# pcb_univ_3-_2-7_-_5-0_-x-rev4.net
KiCad netlist of a schematic drawn in EAGLE
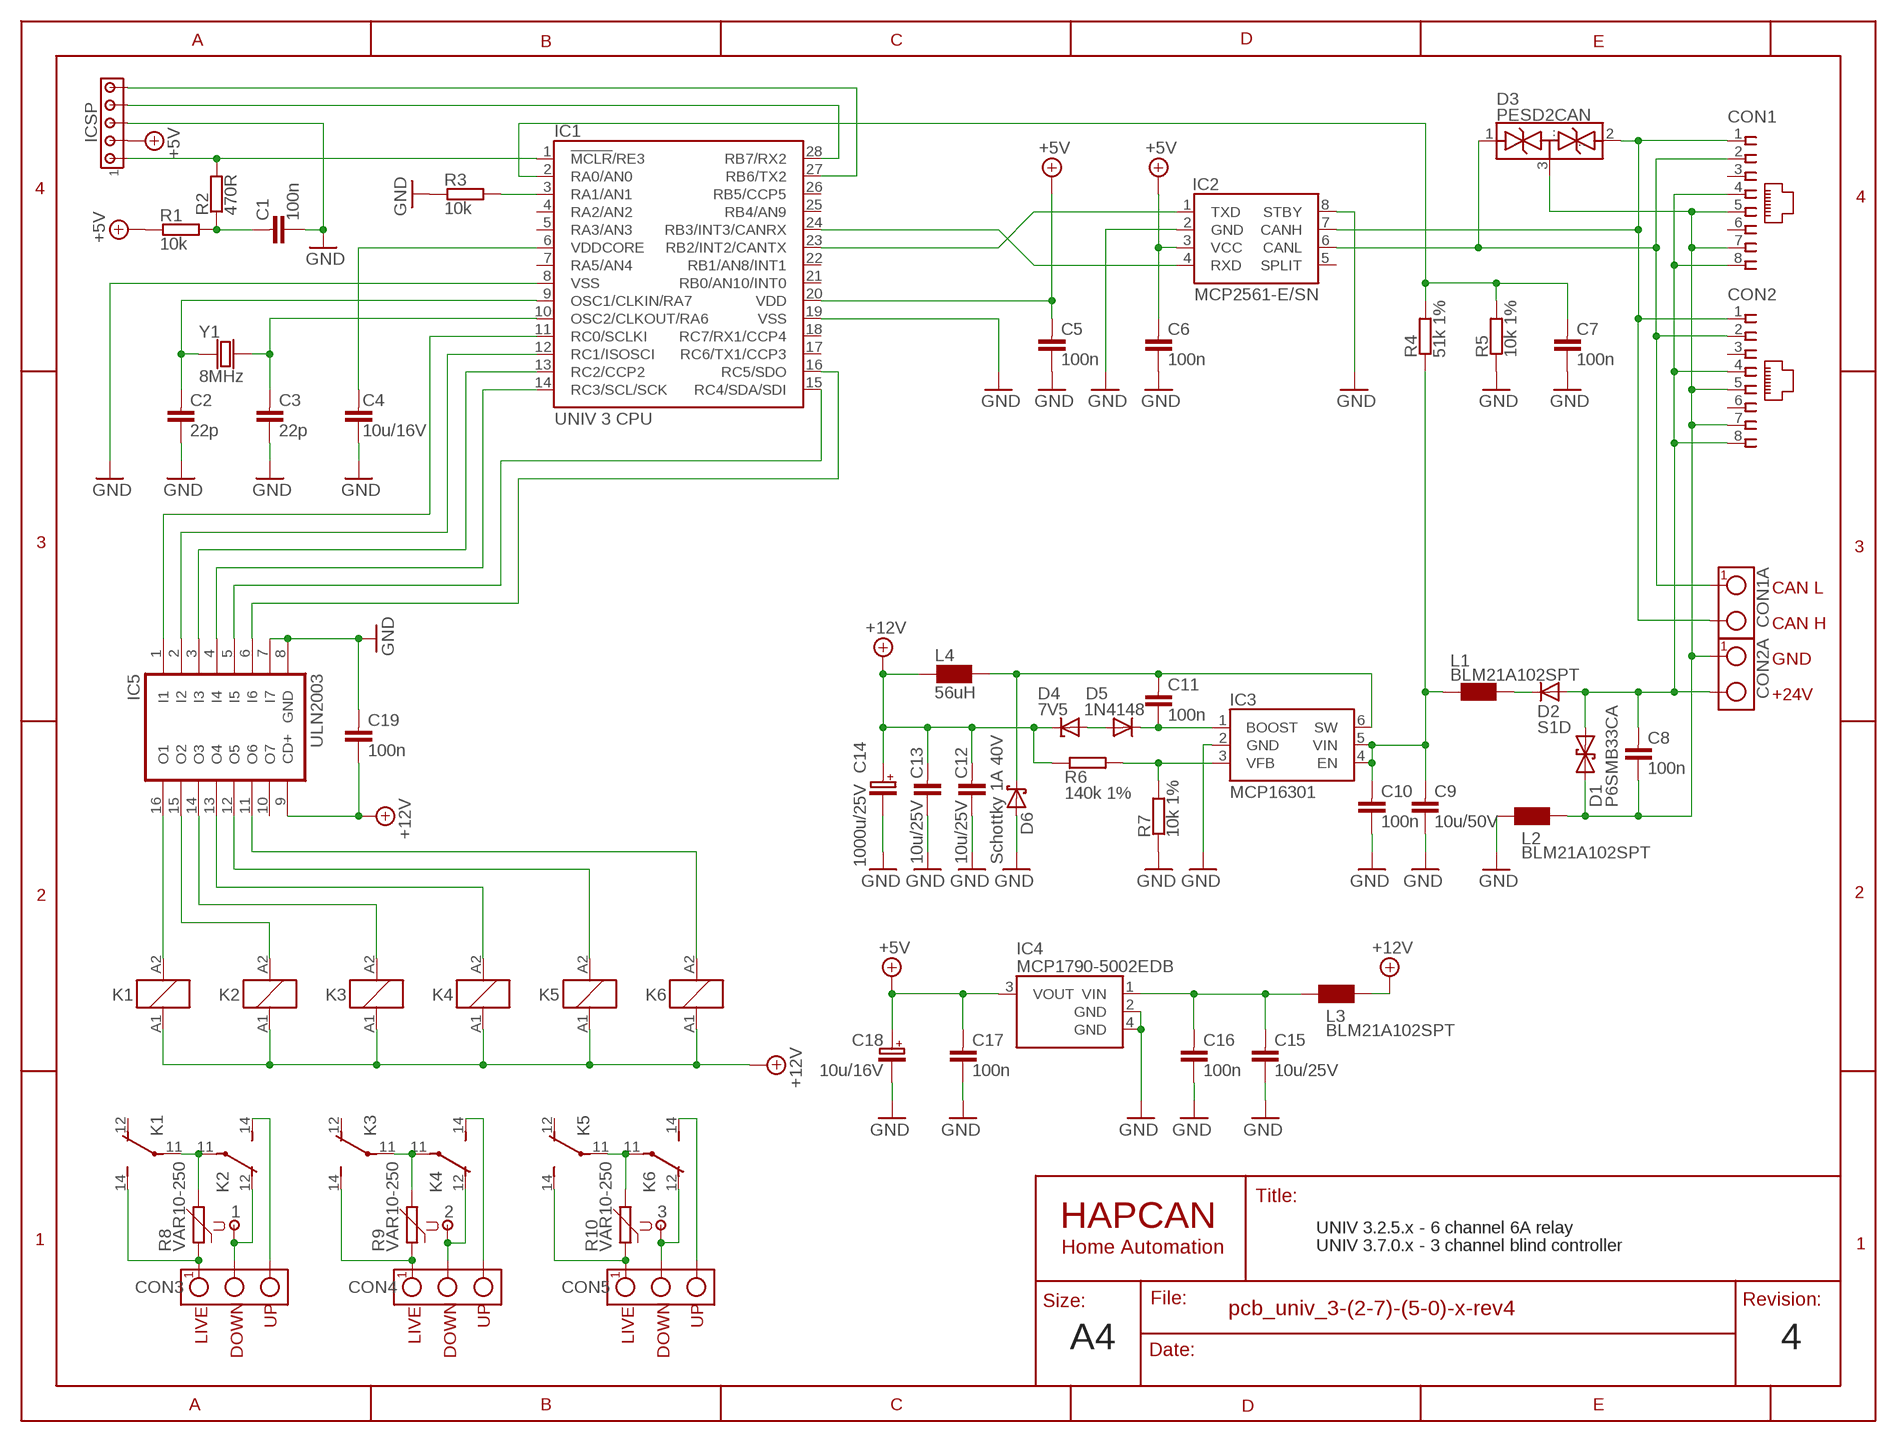
[diagram p0: schematic, sheet 1]

(export (version "E")
  (design (tool "Eeschema 10.0.6"))
  (components
    (comp (ref "1")
      (value "HEADER11X0.9")
      (footprint "eagle-import:SIP-1")
      (libsource (lib "eagle-import") (part "HEADER11X0.9"))
    )
    (comp (ref "2")
      (value "HEADER11X0.9")
      (footprint "eagle-import:SIP-1")
      (libsource (lib "eagle-import") (part "HEADER11X0.9"))
    )
    (comp (ref "3")
      (value "HEADER11X0.9")
      (footprint "eagle-import:SIP-1")
      (libsource (lib "eagle-import") (part "HEADER11X0.9"))
    )
    (comp (ref "C1")
      (value "100n")
      (footprint "eagle-import:0805")
      (libsource (lib "eagle-import") (part "CAPACITOR0805"))
    )
    (comp (ref "C2")
      (value "22p")
      (footprint "eagle-import:0805")
      (libsource (lib "eagle-import") (part "CAPACITOR0805"))
    )
    (comp (ref "C3")
      (value "22p")
      (footprint "eagle-import:0805")
      (libsource (lib "eagle-import") (part "CAPACITOR0805"))
    )
    (comp (ref "C4")
      (value "10u/16V")
      (footprint "eagle-import:0805")
      (libsource (lib "eagle-import") (part "CAPACITOR0805"))
    )
    (comp (ref "C5")
      (value "100n")
      (footprint "eagle-import:0805")
      (libsource (lib "eagle-import") (part "CAPACITOR0805"))
    )
    (comp (ref "C6")
      (value "100n")
      (footprint "eagle-import:0805")
      (libsource (lib "eagle-import") (part "CAPACITOR0805"))
    )
    (comp (ref "C7")
      (value "100n")
      (footprint "eagle-import:0805")
      (libsource (lib "eagle-import") (part "CAPACITOR0805"))
    )
    (comp (ref "C8")
      (value "100n")
      (footprint "eagle-import:0805")
      (libsource (lib "eagle-import") (part "CAPACITOR0805"))
    )
    (comp (ref "C9")
      (value "10u/50V")
      (footprint "eagle-import:1210")
      (libsource (lib "eagle-import") (part "CAPACITOR1210"))
    )
    (comp (ref "C10")
      (value "100n")
      (footprint "eagle-import:0805")
      (libsource (lib "eagle-import") (part "CAPACITOR0805"))
    )
    (comp (ref "C11")
      (value "100n")
      (footprint "eagle-import:0805")
      (libsource (lib "eagle-import") (part "CAPACITOR0805"))
    )
    (comp (ref "C12")
      (value "10u/25V")
      (footprint "eagle-import:1206")
      (libsource (lib "eagle-import") (part "CAPACITOR1206"))
    )
    (comp (ref "C13")
      (value "10u/25V")
      (footprint "eagle-import:1206")
      (libsource (lib "eagle-import") (part "CAPACITOR1206"))
    )
    (comp (ref "C14")
      (value "1000u/25V")
      (footprint "eagle-import:CAP-5X10.5")
      (libsource (lib "eagle-import") (part "CAPACITOR-POLARIZED-5X10.5"))
    )
    (comp (ref "C15")
      (value "10u/25V")
      (footprint "eagle-import:1206")
      (libsource (lib "eagle-import") (part "CAPACITOR1206"))
    )
    (comp (ref "C16")
      (value "100n")
      (footprint "eagle-import:0805")
      (libsource (lib "eagle-import") (part "CAPACITOR0805"))
    )
    (comp (ref "C17")
      (value "100n")
      (footprint "eagle-import:0805")
      (libsource (lib "eagle-import") (part "CAPACITOR0805"))
    )
    (comp (ref "C18")
      (value "10u/16V")
      (footprint "eagle-import:SMC_B")
      (libsource (lib "eagle-import") (part "CAPACITOR-POLARIZED-SMC_B"))
    )
    (comp (ref "C19")
      (value "100n")
      (footprint "eagle-import:0805")
      (libsource (lib "eagle-import") (part "CAPACITOR0805"))
    )
    (comp (ref "CON1")
      (value "RJ45-SOCKET")
      (footprint "eagle-import:RJ45-PCB-SOCKET")
      (libsource (lib "eagle-import") (part "RJ45-SOCKET"))
    )
    (comp (ref "CON1A")
      (value "TERMINAL-2")
      (footprint "eagle-import:ARK2-5X10,5MM")
      (libsource (lib "eagle-import") (part "TERMINAL-2-5X10,5MM"))
    )
    (comp (ref "CON2")
      (value "RJ45-SOCKET")
      (footprint "eagle-import:RJ45-PCB-SOCKET")
      (libsource (lib "eagle-import") (part "RJ45-SOCKET"))
    )
    (comp (ref "CON2A")
      (value "TERMINAL-2")
      (footprint "eagle-import:ARK2-5X10,5MM")
      (libsource (lib "eagle-import") (part "TERMINAL-2-5X10,5MM"))
    )
    (comp (ref "CON3")
      (value "TERMINAL-3-5X10.5MM")
      (footprint "eagle-import:ARK3-5X10.5MM")
      (libsource (lib "eagle-import") (part "TERMINAL-3-5X10.5MM"))
    )
    (comp (ref "CON4")
      (value "TERMINAL-3-5X10.5MM")
      (footprint "eagle-import:ARK3-5X10.5MM")
      (libsource (lib "eagle-import") (part "TERMINAL-3-5X10.5MM"))
    )
    (comp (ref "CON5")
      (value "TERMINAL-3-5X10.5MM")
      (footprint "eagle-import:ARK3-5X10.5MM")
      (libsource (lib "eagle-import") (part "TERMINAL-3-5X10.5MM"))
    )
    (comp (ref "D1")
      (value "P6SMB33CA")
      (footprint "eagle-import:DO-214_TRANSIL2")
      (libsource (lib "eagle-import") (part "DIODE_TRANSIL2"))
    )
    (comp (ref "D2")
      (value "S1D")
      (footprint "eagle-import:DO-214")
      (libsource (lib "eagle-import") (part "DIODE_DO-214"))
    )
    (comp (ref "D3")
      (value "PESD2CAN")
      (footprint "eagle-import:SOT-23")
      (libsource (lib "eagle-import") (part "PESD2CANSOT-23"))
    )
    (comp (ref "D4")
      (value "7V5")
      (footprint "eagle-import:SOD-80")
      (libsource (lib "eagle-import") (part "DIODE_ZENER_SOD-80"))
    )
    (comp (ref "D5")
      (value "1N4148")
      (footprint "eagle-import:0805")
      (libsource (lib "eagle-import") (part "DIODE_0805"))
    )
    (comp (ref "D6")
      (value "Schottky 1A 40V")
      (footprint "eagle-import:DO-214")
      (libsource (lib "eagle-import") (part "DIODE_TRANSIL1_DO214"))
    )
    (comp (ref "IC1")
      (value "UNIV 3 CPU")
      (footprint "eagle-import:UNIV3CPU")
      (libsource (lib "eagle-import") (part "UNIV3CPU-I/SO"))
    )
    (comp (ref "IC2")
      (value "MCP2561-E/SN")
      (footprint "eagle-import:SO-08")
      (libsource (lib "eagle-import") (part "MCP2561-E/SN"))
    )
    (comp (ref "IC3")
      (value "MCP16301")
      (footprint "eagle-import:SOT-23-6")
      (libsource (lib "eagle-import") (part "MCP16301SOT23-6"))
    )
    (comp (ref "IC4")
      (value "MCP1790-5002EDB")
      (footprint "eagle-import:SOT-223")
      (libsource (lib "eagle-import") (part "MCP1826SOT223-3"))
    )
    (comp (ref "IC5")
      (value "ULN2003")
      (footprint "eagle-import:SO-16")
      (libsource (lib "eagle-import") (part "ULN2003"))
    )
    (comp (ref "ICSP")
      (value "HEADER5")
      (footprint "eagle-import:SIP-5")
      (libsource (lib "eagle-import") (part "HEADER5"))
    )
    (comp (ref "K1")
      (value "RELAY_SNR_SPDTV")
      (footprint "eagle-import:RELAY_SNR_SPDT_V")
      (libsource (lib "eagle-import") (part "RELAY_SNR_SPDTV"))
    )
    (comp (ref "K2")
      (value "RELAY_SNR_SPDTV")
      (footprint "eagle-import:RELAY_SNR_SPDT_V")
      (libsource (lib "eagle-import") (part "RELAY_SNR_SPDTV"))
    )
    (comp (ref "K3")
      (value "RELAY_SNR_SPDTV")
      (footprint "eagle-import:RELAY_SNR_SPDT_V")
      (libsource (lib "eagle-import") (part "RELAY_SNR_SPDTV"))
    )
    (comp (ref "K4")
      (value "RELAY_SNR_SPDTV")
      (footprint "eagle-import:RELAY_SNR_SPDT_V")
      (libsource (lib "eagle-import") (part "RELAY_SNR_SPDTV"))
    )
    (comp (ref "K5")
      (value "RELAY_SNR_SPDTV")
      (footprint "eagle-import:RELAY_SNR_SPDT_V")
      (libsource (lib "eagle-import") (part "RELAY_SNR_SPDTV"))
    )
    (comp (ref "K6")
      (value "RELAY_SNR_SPDTV")
      (footprint "eagle-import:RELAY_SNR_SPDT_V")
      (libsource (lib "eagle-import") (part "RELAY_SNR_SPDTV"))
    )
    (comp (ref "L1")
      (value "BLM21A102SPT")
      (footprint "eagle-import:0805")
      (libsource (lib "eagle-import") (part "CHOKE0805"))
    )
    (comp (ref "L2")
      (value "BLM21A102SPT")
      (footprint "eagle-import:0805")
      (libsource (lib "eagle-import") (part "CHOKE0805"))
    )
    (comp (ref "L3")
      (value "BLM21A102SPT")
      (footprint "eagle-import:0805")
      (libsource (lib "eagle-import") (part "CHOKE0805"))
    )
    (comp (ref "L4")
      (value "56uH")
      (footprint "eagle-import:CHOKE-DER0705")
      (libsource (lib "eagle-import") (part "CHOKEDER0705"))
    )
    (comp (ref "R1")
      (value "10k")
      (footprint "eagle-import:0805")
      (libsource (lib "eagle-import") (part "RESISTOR0805"))
    )
    (comp (ref "R2")
      (value "470R")
      (footprint "eagle-import:0805")
      (libsource (lib "eagle-import") (part "RESISTOR0805"))
    )
    (comp (ref "R3")
      (value "10k")
      (footprint "eagle-import:0805")
      (libsource (lib "eagle-import") (part "RESISTOR0805"))
    )
    (comp (ref "R4")
      (value "51k 1%")
      (footprint "eagle-import:0805")
      (libsource (lib "eagle-import") (part "RESISTOR0805"))
    )
    (comp (ref "R5")
      (value "10k 1%")
      (footprint "eagle-import:0805")
      (libsource (lib "eagle-import") (part "RESISTOR0805"))
    )
    (comp (ref "R6")
      (value "140k 1%")
      (footprint "eagle-import:0805")
      (libsource (lib "eagle-import") (part "RESISTOR0805"))
    )
    (comp (ref "R7")
      (value "10k 1%")
      (footprint "eagle-import:0805")
      (libsource (lib "eagle-import") (part "RESISTOR0805"))
    )
    (comp (ref "R8")
      (value "VAR10-250")
      (footprint "eagle-import:VARISTOR1")
      (libsource (lib "eagle-import") (part "VARISTOR7.5MM-1"))
    )
    (comp (ref "R9")
      (value "VAR10-250")
      (footprint "eagle-import:VARISTOR1")
      (libsource (lib "eagle-import") (part "VARISTOR7.5MM-1"))
    )
    (comp (ref "R10")
      (value "VAR10-250")
      (footprint "eagle-import:VARISTOR1")
      (libsource (lib "eagle-import") (part "VARISTOR7.5MM-1"))
    )
    (comp (ref "Y1")
      (value "8MHz")
      (footprint "eagle-import:CRYSTAL-HC49V")
      (libsource (lib "eagle-import") (part "CRYSTAL-HC49V"))
    )
  )
  (nets
    (net (code "1") (name "+5V") (class "Default")
      (node (ref "C17") (pin "1") (pinfunction "1_1") (pintype "passive"))
      (node (ref "C18") (pin "+") (pinfunction "1_+") (pintype "passive"))
      (node (ref "C5") (pin "1") (pinfunction "1_1") (pintype "passive"))
      (node (ref "C6") (pin "1") (pinfunction "1_1") (pintype "passive"))
      (node (ref "IC1") (pin "20") (pinfunction "VDD_20") (pintype "bidirectional"))
      (node (ref "IC2") (pin "3") (pinfunction "VCC_3") (pintype "bidirectional"))
      (node (ref "IC4") (pin "3") (pinfunction "VOUT_3") (pintype "bidirectional"))
      (node (ref "ICSP") (pin "2") (pinfunction "2_2") (pintype "passive"))
      (node (ref "R1") (pin "1") (pinfunction "1_1") (pintype "passive"))
    )
    (net (code "2") (name "+12V") (class "Default")
      (node (ref "C12") (pin "1") (pinfunction "1_1") (pintype "passive"))
      (node (ref "C13") (pin "1") (pinfunction "1_1") (pintype "passive"))
      (node (ref "C14") (pin "+") (pinfunction "1_+") (pintype "passive"))
      (node (ref "C19") (pin "2") (pinfunction "2_2") (pintype "passive"))
      (node (ref "D4") (pin "C") (pinfunction "C_C") (pintype "passive"))
      (node (ref "IC5") (pin "9") (pinfunction "CD+_9") (pintype "passive"))
      (node (ref "K1") (pin "A1") (pinfunction "1_A1") (pintype "passive"))
      (node (ref "K2") (pin "A1") (pinfunction "1_A1") (pintype "passive"))
      (node (ref "K3") (pin "A1") (pinfunction "1_A1") (pintype "passive"))
      (node (ref "K4") (pin "A1") (pinfunction "1_A1") (pintype "passive"))
      (node (ref "K5") (pin "A1") (pinfunction "1_A1") (pintype "passive"))
      (node (ref "K6") (pin "A1") (pinfunction "1_A1") (pintype "passive"))
      (node (ref "L3") (pin "2") (pinfunction "2_2") (pintype "passive"))
      (node (ref "L4") (pin "1") (pinfunction "1_1") (pintype "passive"))
      (node (ref "R6") (pin "1") (pinfunction "1_1") (pintype "passive"))
    )
    (net (code "3") (name "GND") (class "Default")
      (node (ref "C1") (pin "2") (pinfunction "2_2") (pintype "passive"))
      (node (ref "C10") (pin "2") (pinfunction "2_2") (pintype "passive"))
      (node (ref "C12") (pin "2") (pinfunction "2_2") (pintype "passive"))
      (node (ref "C13") (pin "2") (pinfunction "2_2") (pintype "passive"))
      (node (ref "C14") (pin "-") (pinfunction "2_-") (pintype "passive"))
      (node (ref "C15") (pin "2") (pinfunction "2_2") (pintype "passive"))
      (node (ref "C16") (pin "2") (pinfunction "2_2") (pintype "passive"))
      (node (ref "C17") (pin "2") (pinfunction "2_2") (pintype "passive"))
      (node (ref "C18") (pin "-") (pinfunction "2_-") (pintype "passive"))
      (node (ref "C19") (pin "1") (pinfunction "1_1") (pintype "passive"))
      (node (ref "C2") (pin "2") (pinfunction "2_2") (pintype "passive"))
      (node (ref "C3") (pin "2") (pinfunction "2_2") (pintype "passive"))
      (node (ref "C4") (pin "2") (pinfunction "2_2") (pintype "passive"))
      (node (ref "C5") (pin "2") (pinfunction "2_2") (pintype "passive"))
      (node (ref "C6") (pin "2") (pinfunction "2_2") (pintype "passive"))
      (node (ref "C7") (pin "2") (pinfunction "2_2") (pintype "passive"))
      (node (ref "C9") (pin "2") (pinfunction "2_2") (pintype "passive"))
      (node (ref "D6") (pin "A") (pinfunction "A_A") (pintype "passive"))
      (node (ref "IC1") (pin "19") (pinfunction "VSS_19") (pintype "bidirectional"))
      (node (ref "IC1") (pin "8") (pinfunction "VSS_8") (pintype "bidirectional"))
      (node (ref "IC2") (pin "2") (pinfunction "GND_2") (pintype "bidirectional"))
      (node (ref "IC2") (pin "8") (pinfunction "STBY_8") (pintype "bidirectional"))
      (node (ref "IC3") (pin "2") (pinfunction "GND_2") (pintype "bidirectional"))
      (node (ref "IC4") (pin "2") (pinfunction "GND_2") (pintype "bidirectional"))
      (node (ref "IC4") (pin "4") (pinfunction "GND_4") (pintype "bidirectional"))
      (node (ref "IC5") (pin "7") (pinfunction "I7_7") (pintype "input"))
      (node (ref "IC5") (pin "8") (pinfunction "GND_8") (pintype "power_in"))
      (node (ref "ICSP") (pin "3") (pinfunction "3_3") (pintype "passive"))
      (node (ref "L2") (pin "1") (pinfunction "1_1") (pintype "passive"))
      (node (ref "R3") (pin "1") (pinfunction "1_1") (pintype "passive"))
      (node (ref "R5") (pin "1") (pinfunction "1_1") (pintype "passive"))
      (node (ref "R7") (pin "1") (pinfunction "1_1") (pintype "passive"))
    )
    (net (code "4") (name "Net-(C1-Pad1)") (class "Default")
      (node (ref "C1") (pin "1") (pinfunction "1_1") (pintype "passive"))
      (node (ref "R1") (pin "2") (pinfunction "2_2") (pintype "passive"))
      (node (ref "R2") (pin "1") (pinfunction "1_1") (pintype "passive"))
    )
    (net (code "5") (name "Net-(D1-1)") (class "Default")
      (node (ref "C8") (pin "2") (pinfunction "2_2") (pintype "passive"))
      (node (ref "CON1") (pin "5") (pinfunction "5_5") (pintype "passive"))
      (node (ref "CON1") (pin "7") (pinfunction "7_7") (pintype "passive"))
      (node (ref "CON2") (pin "5") (pinfunction "5_5") (pintype "passive"))
      (node (ref "CON2") (pin "7") (pinfunction "7_7") (pintype "passive"))
      (node (ref "CON2A") (pin "1") (pinfunction "1_1") (pintype "passive"))
      (node (ref "D1") (pin "A") (pinfunction "1_A") (pintype "passive"))
      (node (ref "D3") (pin "3") (pinfunction "..._3") (pintype "bidirectional"))
      (node (ref "L2") (pin "2") (pinfunction "2_2") (pintype "passive"))
    )
    (net (code "6") (name "Net-(D1-2)") (class "Default")
      (node (ref "C8") (pin "1") (pinfunction "1_1") (pintype "passive"))
      (node (ref "CON1") (pin "4") (pinfunction "4_4") (pintype "passive"))
      (node (ref "CON1") (pin "8") (pinfunction "8_8") (pintype "passive"))
      (node (ref "CON2") (pin "4") (pinfunction "4_4") (pintype "passive"))
      (node (ref "CON2") (pin "8") (pinfunction "8_8") (pintype "passive"))
      (node (ref "CON2A") (pin "2") (pinfunction "2_2") (pintype "passive"))
      (node (ref "D1") (pin "C") (pinfunction "2_C") (pintype "passive"))
      (node (ref "D2") (pin "A") (pinfunction "A_A") (pintype "passive"))
    )
    (net (code "7") (name "Net-(D2-PadC)") (class "Default")
      (node (ref "D2") (pin "C") (pinfunction "C_C") (pintype "passive"))
      (node (ref "L1") (pin "2") (pinfunction "2_2") (pintype "passive"))
    )
    (net (code "8") (name "Net-(D3-.)") (class "Default")
      (node (ref "CON1") (pin "2") (pinfunction "2_2") (pintype "passive"))
      (node (ref "CON1A") (pin "1") (pinfunction "1_1") (pintype "passive"))
      (node (ref "CON2") (pin "2") (pinfunction "2_2") (pintype "passive"))
      (node (ref "D3") (pin "1") (pinfunction "._1") (pintype "bidirectional"))
      (node (ref "IC2") (pin "6") (pinfunction "CANL_6") (pintype "bidirectional"))
    )
    (net (code "9") (name "Net-(D3-..)") (class "Default")
      (node (ref "CON1") (pin "1") (pinfunction "1_1") (pintype "passive"))
      (node (ref "CON1A") (pin "2") (pinfunction "2_2") (pintype "passive"))
      (node (ref "CON2") (pin "1") (pinfunction "1_1") (pintype "passive"))
      (node (ref "D3") (pin "2") (pinfunction ".._2") (pintype "bidirectional"))
      (node (ref "IC2") (pin "7") (pinfunction "CANH_7") (pintype "bidirectional"))
    )
    (net (code "10") (name "Net-(D5-A)") (class "Default")
      (node (ref "D4") (pin "A") (pinfunction "A_A") (pintype "passive"))
      (node (ref "D5") (pin "2") (pinfunction "A_2") (pintype "passive"))
    )
    (net (code "11") (name "Net-(D5-C)") (class "Default")
      (node (ref "C11") (pin "2") (pinfunction "2_2") (pintype "passive"))
      (node (ref "D5") (pin "1") (pinfunction "C_1") (pintype "passive"))
      (node (ref "IC3") (pin "1") (pinfunction "BOOST_1") (pintype "bidirectional"))
    )
    (net (code "12") (name "Net-(IC1-OSC1{slash}CLKIN{slash}RA7)") (class "Default")
      (node (ref "C2") (pin "1") (pinfunction "1_1") (pintype "passive"))
      (node (ref "IC1") (pin "9") (pinfunction "OSC1/CLKIN/RA7_9") (pintype "bidirectional"))
      (node (ref "Y1") (pin "1") (pinfunction "1_1") (pintype "passive"))
    )
    (net (code "13") (name "Net-(IC1-OSC2{slash}CLKOUT{slash}RA6)") (class "Default")
      (node (ref "C3") (pin "1") (pinfunction "1_1") (pintype "passive"))
      (node (ref "IC1") (pin "10") (pinfunction "OSC2/CLKOUT/RA6_10") (pintype "bidirectional"))
      (node (ref "Y1") (pin "2") (pinfunction "2_2") (pintype "passive"))
    )
    (net (code "14") (name "Net-(IC1-RA0{slash}AN0)") (class "Default")
      (node (ref "C7") (pin "1") (pinfunction "1_1") (pintype "passive"))
      (node (ref "IC1") (pin "2") (pinfunction "RA0/AN0_2") (pintype "bidirectional"))
      (node (ref "R4") (pin "2") (pinfunction "2_2") (pintype "passive"))
      (node (ref "R5") (pin "2") (pinfunction "2_2") (pintype "passive"))
    )
    (net (code "15") (name "Net-(IC1-RA1{slash}AN1)") (class "Default")
      (node (ref "IC1") (pin "3") (pinfunction "RA1/AN1_3") (pintype "bidirectional"))
      (node (ref "R3") (pin "2") (pinfunction "2_2") (pintype "passive"))
    )
    (net (code "16") (name "Net-(IC1-RB2{slash}INT2{slash}CANTX)") (class "Default")
      (node (ref "IC1") (pin "23") (pinfunction "RB2/INT2/CANTX_23") (pintype "bidirectional"))
      (node (ref "IC2") (pin "1") (pinfunction "TXD_1") (pintype "bidirectional"))
    )
    (net (code "17") (name "Net-(IC1-RB3{slash}INT3{slash}CANRX)") (class "Default")
      (node (ref "IC1") (pin "24") (pinfunction "RB3/INT3/CANRX_24") (pintype "bidirectional"))
      (node (ref "IC2") (pin "4") (pinfunction "RXD_4") (pintype "bidirectional"))
    )
    (net (code "18") (name "Net-(IC1-RB6{slash}TX2)") (class "Default")
      (node (ref "IC1") (pin "27") (pinfunction "RB6/TX2_27") (pintype "bidirectional"))
      (node (ref "ICSP") (pin "5") (pinfunction "5_5") (pintype "passive"))
    )
    (net (code "19") (name "Net-(IC1-RB7{slash}RX2)") (class "Default")
      (node (ref "IC1") (pin "28") (pinfunction "RB7/RX2_28") (pintype "bidirectional"))
      (node (ref "ICSP") (pin "4") (pinfunction "4_4") (pintype "passive"))
    )
    (net (code "20") (name "Net-(IC1-RC0{slash}SCLKI)") (class "Default")
      (node (ref "IC1") (pin "11") (pinfunction "RC0/SCLKI_11") (pintype "bidirectional"))
      (node (ref "IC5") (pin "1") (pinfunction "I1_1") (pintype "input"))
    )
    (net (code "21") (name "Net-(IC1-RC1{slash}ISOSCI)") (class "Default")
      (node (ref "IC1") (pin "12") (pinfunction "RC1/ISOSCI_12") (pintype "bidirectional"))
      (node (ref "IC5") (pin "2") (pinfunction "I2_2") (pintype "input"))
    )
    (net (code "22") (name "Net-(IC1-RC2{slash}CCP2)") (class "Default")
      (node (ref "IC1") (pin "13") (pinfunction "RC2/CCP2_13") (pintype "bidirectional"))
      (node (ref "IC5") (pin "3") (pinfunction "I3_3") (pintype "input"))
    )
    (net (code "23") (name "Net-(IC1-RC3{slash}SCL{slash}SCK)") (class "Default")
      (node (ref "IC1") (pin "14") (pinfunction "RC3/SCL/SCK_14") (pintype "bidirectional"))
      (node (ref "IC5") (pin "4") (pinfunction "I4_4") (pintype "input"))
    )
    (net (code "24") (name "Net-(IC1-RC4{slash}SDA{slash}SDI)") (class "Default")
      (node (ref "IC1") (pin "15") (pinfunction "RC4/SDA/SDI_15") (pintype "bidirectional"))
      (node (ref "IC5") (pin "5") (pinfunction "I5_5") (pintype "input"))
    )
    (net (code "25") (name "Net-(IC1-RC5{slash}SDO)") (class "Default")
      (node (ref "IC1") (pin "16") (pinfunction "RC5/SDO_16") (pintype "bidirectional"))
      (node (ref "IC5") (pin "6") (pinfunction "I6_6") (pintype "input"))
    )
    (net (code "26") (name "Net-(IC1-VDDCORE)") (class "Default")
      (node (ref "C4") (pin "1") (pinfunction "1_1") (pintype "passive"))
      (node (ref "IC1") (pin "6") (pinfunction "VDDCORE_6") (pintype "bidirectional"))
    )
    (net (code "27") (name "Net-(IC1-~{MCLR}{slash}RE3)") (class "Default")
      (node (ref "IC1") (pin "1") (pinfunction "~{MCLR}/RE3_1") (pintype "bidirectional"))
      (node (ref "ICSP") (pin "1") (pinfunction "1_1") (pintype "passive"))
      (node (ref "R2") (pin "2") (pinfunction "2_2") (pintype "passive"))
    )
    (net (code "28") (name "Net-(IC3-EN)") (class "Default")
      (node (ref "C10") (pin "1") (pinfunction "1_1") (pintype "passive"))
      (node (ref "C9") (pin "1") (pinfunction "1_1") (pintype "passive"))
      (node (ref "IC3") (pin "4") (pinfunction "EN_4") (pintype "bidirectional"))
      (node (ref "IC3") (pin "5") (pinfunction "VIN_5") (pintype "bidirectional"))
      (node (ref "L1") (pin "1") (pinfunction "1_1") (pintype "passive"))
      (node (ref "R4") (pin "1") (pinfunction "1_1") (pintype "passive"))
    )
    (net (code "29") (name "Net-(IC3-SW)") (class "Default")
      (node (ref "C11") (pin "1") (pinfunction "1_1") (pintype "passive"))
      (node (ref "D6") (pin "C") (pinfunction "C_C") (pintype "passive"))
      (node (ref "IC3") (pin "6") (pinfunction "SW_6") (pintype "bidirectional"))
      (node (ref "L4") (pin "2") (pinfunction "2_2") (pintype "passive"))
    )
    (net (code "30") (name "Net-(IC3-VFB)") (class "Default")
      (node (ref "IC3") (pin "3") (pinfunction "VFB_3") (pintype "bidirectional"))
      (node (ref "R6") (pin "2") (pinfunction "2_2") (pintype "passive"))
      (node (ref "R7") (pin "2") (pinfunction "2_2") (pintype "passive"))
    )
    (net (code "31") (name "Net-(IC4-VIN)") (class "Default")
      (node (ref "C15") (pin "1") (pinfunction "1_1") (pintype "passive"))
      (node (ref "C16") (pin "1") (pinfunction "1_1") (pintype "passive"))
      (node (ref "IC4") (pin "1") (pinfunction "VIN_1") (pintype "bidirectional"))
      (node (ref "L3") (pin "1") (pinfunction "1_1") (pintype "passive"))
    )
    (net (code "32") (name "Net-(IC5-O1)") (class "Default")
      (node (ref "IC5") (pin "16") (pinfunction "O1_16") (pintype "open_collector"))
      (node (ref "K1") (pin "A2") (pinfunction "2_A2") (pintype "passive"))
    )
    (net (code "33") (name "Net-(IC5-O2)") (class "Default")
      (node (ref "IC5") (pin "15") (pinfunction "O2_15") (pintype "open_collector"))
      (node (ref "K2") (pin "A2") (pinfunction "2_A2") (pintype "passive"))
    )
    (net (code "34") (name "Net-(IC5-O3)") (class "Default")
      (node (ref "IC5") (pin "14") (pinfunction "O3_14") (pintype "open_collector"))
      (node (ref "K3") (pin "A2") (pinfunction "2_A2") (pintype "passive"))
    )
    (net (code "35") (name "Net-(IC5-O4)") (class "Default")
      (node (ref "IC5") (pin "13") (pinfunction "O4_13") (pintype "open_collector"))
      (node (ref "K4") (pin "A2") (pinfunction "2_A2") (pintype "passive"))
    )
    (net (code "36") (name "Net-(IC5-O5)") (class "Default")
      (node (ref "IC5") (pin "12") (pinfunction "O5_12") (pintype "open_collector"))
      (node (ref "K5") (pin "A2") (pinfunction "2_A2") (pintype "passive"))
    )
    (net (code "37") (name "Net-(IC5-O6)") (class "Default")
      (node (ref "IC5") (pin "11") (pinfunction "O6_11") (pintype "open_collector"))
      (node (ref "K6") (pin "A2") (pinfunction "2_A2") (pintype "passive"))
    )
    (net (code "38") (name "Net-(K1B-COM)") (class "Default")
      (node (ref "K1") (pin "11") (pinfunction "COM_11") (pintype "passive"))
      (node (ref "K2") (pin "11") (pinfunction "COM_11") (pintype "passive"))
      (node (ref "R8") (pin "2") (pinfunction "2_2") (pintype "passive"))
    )
    (net (code "39") (name "Net-(K1B-NO)") (class "Default")
      (node (ref "CON3") (pin "1") (pinfunction "1_1") (pintype "passive"))
      (node (ref "K1") (pin "14") (pinfunction "NO_14") (pintype "passive"))
      (node (ref "R8") (pin "1") (pinfunction "1_1") (pintype "passive"))
    )
    (net (code "40") (name "Net-(K2B-NC)") (class "Default")
      (node (ref "1") (pin "1") (pinfunction "1_1") (pintype "passive"))
      (node (ref "CON3") (pin "2") (pinfunction "2_2") (pintype "passive"))
      (node (ref "K2") (pin "12") (pinfunction "NC_12") (pintype "passive"))
    )
    (net (code "41") (name "Net-(K2B-NO)") (class "Default")
      (node (ref "CON3") (pin "3") (pinfunction "3_3") (pintype "passive"))
      (node (ref "K2") (pin "14") (pinfunction "NO_14") (pintype "passive"))
    )
    (net (code "42") (name "Net-(K3B-COM)") (class "Default")
      (node (ref "K3") (pin "11") (pinfunction "COM_11") (pintype "passive"))
      (node (ref "K4") (pin "11") (pinfunction "COM_11") (pintype "passive"))
      (node (ref "R9") (pin "2") (pinfunction "2_2") (pintype "passive"))
    )
    (net (code "43") (name "Net-(K3B-NO)") (class "Default")
      (node (ref "CON4") (pin "1") (pinfunction "1_1") (pintype "passive"))
      (node (ref "K3") (pin "14") (pinfunction "NO_14") (pintype "passive"))
      (node (ref "R9") (pin "1") (pinfunction "1_1") (pintype "passive"))
    )
    (net (code "44") (name "Net-(K4B-NC)") (class "Default")
      (node (ref "2") (pin "1") (pinfunction "1_1") (pintype "passive"))
      (node (ref "CON4") (pin "2") (pinfunction "2_2") (pintype "passive"))
      (node (ref "K4") (pin "12") (pinfunction "NC_12") (pintype "passive"))
    )
    (net (code "45") (name "Net-(K4B-NO)") (class "Default")
      (node (ref "CON4") (pin "3") (pinfunction "3_3") (pintype "passive"))
      (node (ref "K4") (pin "14") (pinfunction "NO_14") (pintype "passive"))
    )
    (net (code "46") (name "Net-(K5B-COM)") (class "Default")
      (node (ref "K5") (pin "11") (pinfunction "COM_11") (pintype "passive"))
      (node (ref "K6") (pin "11") (pinfunction "COM_11") (pintype "passive"))
      (node (ref "R10") (pin "2") (pinfunction "2_2") (pintype "passive"))
    )
    (net (code "47") (name "Net-(K5B-NO)") (class "Default")
      (node (ref "CON5") (pin "1") (pinfunction "1_1") (pintype "passive"))
      (node (ref "K5") (pin "14") (pinfunction "NO_14") (pintype "passive"))
      (node (ref "R10") (pin "1") (pinfunction "1_1") (pintype "passive"))
    )
    (net (code "48") (name "Net-(K6B-NC)") (class "Default")
      (node (ref "3") (pin "1") (pinfunction "1_1") (pintype "passive"))
      (node (ref "CON5") (pin "2") (pinfunction "2_2") (pintype "passive"))
      (node (ref "K6") (pin "12") (pinfunction "NC_12") (pintype "passive"))
    )
    (net (code "49") (name "Net-(K6B-NO)") (class "Default")
      (node (ref "CON5") (pin "3") (pinfunction "3_3") (pintype "passive"))
      (node (ref "K6") (pin "14") (pinfunction "NO_14") (pintype "passive"))
    )
    (net (code "50") (name "unconnected-(CON1-Pad3)") (class "Default")
      (node (ref "CON1") (pin "3") (pinfunction "3_3") (pintype "passive"))
    )
    (net (code "51") (name "unconnected-(CON1-Pad6)") (class "Default")
      (node (ref "CON1") (pin "6") (pinfunction "6_6") (pintype "passive"))
    )
    (net (code "52") (name "unconnected-(CON2-Pad3)") (class "Default")
      (node (ref "CON2") (pin "3") (pinfunction "3_3") (pintype "passive"))
    )
    (net (code "53") (name "unconnected-(CON2-Pad6)") (class "Default")
      (node (ref "CON2") (pin "6") (pinfunction "6_6") (pintype "passive"))
    )
    (net (code "54") (name "unconnected-(IC1-RA2{slash}AN2-Pad4)") (class "Default")
      (node (ref "IC1") (pin "4") (pinfunction "RA2/AN2_4") (pintype "bidirectional"))
    )
    (net (code "55") (name "unconnected-(IC1-RA3{slash}AN3-Pad5)") (class "Default")
      (node (ref "IC1") (pin "5") (pinfunction "RA3/AN3_5") (pintype "bidirectional"))
    )
    (net (code "56") (name "unconnected-(IC1-RA5{slash}AN4-Pad7)") (class "Default")
      (node (ref "IC1") (pin "7") (pinfunction "RA5/AN4_7") (pintype "bidirectional"))
    )
    (net (code "57") (name "unconnected-(IC1-RB0{slash}AN10{slash}INT0-Pad21)") (class "Default")
      (node (ref "IC1") (pin "21") (pinfunction "RB0/AN10/INT0_21") (pintype "bidirectional"))
    )
    (net (code "58") (name "unconnected-(IC1-RB1{slash}AN8{slash}INT1-Pad22)") (class "Default")
      (node (ref "IC1") (pin "22") (pinfunction "RB1/AN8/INT1_22") (pintype "bidirectional"))
    )
    (net (code "59") (name "unconnected-(IC1-RB4{slash}AN9-Pad25)") (class "Default")
      (node (ref "IC1") (pin "25") (pinfunction "RB4/AN9_25") (pintype "bidirectional"))
    )
    (net (code "60") (name "unconnected-(IC1-RB5{slash}CCP5-Pad26)") (class "Default")
      (node (ref "IC1") (pin "26") (pinfunction "RB5/CCP5_26") (pintype "bidirectional"))
    )
    (net (code "61") (name "unconnected-(IC1-RC6{slash}TX1{slash}CCP3-Pad17)") (class "Default")
      (node (ref "IC1") (pin "17") (pinfunction "RC6/TX1/CCP3_17") (pintype "bidirectional"))
    )
    (net (code "62") (name "unconnected-(IC1-RC7{slash}RX1{slash}CCP4-Pad18)") (class "Default")
      (node (ref "IC1") (pin "18") (pinfunction "RC7/RX1/CCP4_18") (pintype "bidirectional"))
    )
    (net (code "63") (name "unconnected-(IC2-SPLIT-Pad5)") (class "Default")
      (node (ref "IC2") (pin "5") (pinfunction "SPLIT_5") (pintype "bidirectional"))
    )
    (net (code "64") (name "unconnected-(IC5-O7-Pad10)") (class "Default")
      (node (ref "IC5") (pin "10") (pinfunction "O7_10") (pintype "open_collector"))
    )
    (net (code "65") (name "unconnected-(K1B-NC-Pad12)") (class "Default")
      (node (ref "K1") (pin "12") (pinfunction "NC_12") (pintype "passive"))
    )
    (net (code "66") (name "unconnected-(K3B-NC-Pad12)") (class "Default")
      (node (ref "K3") (pin "12") (pinfunction "NC_12") (pintype "passive"))
    )
    (net (code "67") (name "unconnected-(K5B-NC-Pad12)") (class "Default")
      (node (ref "K5") (pin "12") (pinfunction "NC_12") (pintype "passive"))
    )
  )
)
